# Alimentacion.net
KiCad netlist of a schematic drawn in Altium Designer
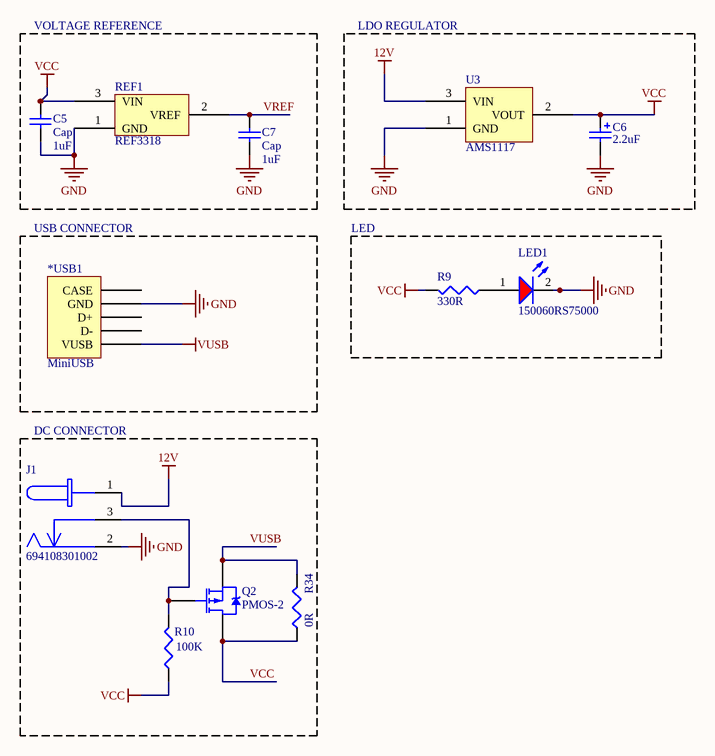
[diagram p0: Alimentacion.SchDoc]

(export (version "E")
  (design (tool "Eeschema 10.0.6"))
  (components
    (comp (ref "*USB1")
      (value "MiniUSB")
      (footprint "Mini USB")
      (description "KYOCERA  24 5141 005 000 863")
      (libsource (lib "Lib_CR") (part "MiniUSB"))
    )
    (comp (ref "C5")
      (value "Cap")
      (footprint "C0805")
      (description "Capacitor")
      (fields (field (name "ALTIUM_VALUE") "1uF") (field (name "PUBLISHER") "Altium Limited"))
      (libsource (lib "Miscellaneous Devices") (part "Cap"))
    )
    (comp (ref "C6")
      (value "2.2uF")
      (footprint "Miscellaneous Devices:C0805")
      (fields (field (name "Comment") "CapPol"))
      (libsource (lib "Library_triggerr") (part "CapPol"))
    )
    (comp (ref "C7")
      (value "Cap")
      (footprint "C0805")
      (description "Capacitor")
      (fields (field (name "ALTIUM_VALUE") "1uF") (field (name "PUBLISHER") "Altium Limited"))
      (libsource (lib "Miscellaneous Devices") (part "Cap"))
    )
    (comp (ref "J1")
      (value "694108301002")
      (footprint "694108301002")
      (description "WR-DC DC Power Jack Right Angled(6.4)")
      (fields (field (name "PUBLISHER") "Wurth Elektronik"))
      (libsource (lib "ALTIUM-WR-DC_POWER_JACK_CONNECTORS-rev1") (part "694108301002"))
    )
    (comp (ref "LED1")
      (value "150060RS75000")
      (footprint "LED_0603_Red")
      (description "SMD mono-color Chip LED, WL-SMCW, Red")
      (fields
        (field (name "MANUFACTURER") "W黵th Elektronik eiSos GmbH")
        (field (name "CREATED BY") "Christin Otto")
      )
      (libsource (lib "WL-SMCW_rev15b") (part "WL-SMCW 0603  150060RS75000"))
    )
    (comp (ref "Q2")
      (value "PMOS-2")
      (footprint "SOT23_N")
      (description "P-Channel Power MOSFET")
      (fields (field (name "PUBLISHER") "Altium Limited"))
      (libsource (lib "Miscellaneous Devices") (part "PMOS-2"))
    )
    (comp (ref "R9")
      (value "330R")
      (footprint "6-0805_N")
      (description "Resistor")
      (fields (field (name "Comment") "Res") (field (name "PUBLISHER") "Altium Limited"))
      (libsource (lib "Miscellaneous Devices") (part "Res3"))
    )
    (comp (ref "R10")
      (value "100K")
      (footprint "6-0805_N")
      (description "Resistor")
      (fields (field (name "Comment") "Res") (field (name "PUBLISHER") "Altium Limited"))
      (libsource (lib "Miscellaneous Devices") (part "Res3"))
    )
    (comp (ref "R34")
      (value "0R")
      (footprint "6-0805_N")
      (description "Resistor")
      (fields (field (name "Comment") "Res") (field (name "PUBLISHER") "Altium Limited"))
      (libsource (lib "Miscellaneous Devices") (part "Res3"))
    )
    (comp (ref "REF1")
      (value "REF3318")
      (footprint "SOT23_N")
      (libsource (lib "Library_triggerr") (part "REF3318"))
    )
    (comp (ref "U3")
      (value "AMS1117")
      (footprint "SOT223_N")
      (libsource (lib "Library_triggerr") (part "AMS1117"))
    )
  )
  (nets
    (net (code "1") (name "/VREF") (class "Default")
      (node (ref "C7") (pin "2") (pinfunction "2_2") (pintype "passive"))
      (node (ref "REF1") (pin "2") (pinfunction "VREF_2") (pintype "passive"))
    )
    (net (code "2") (name "12V") (class "Default")
      (node (ref "J1") (pin "1") (pinfunction "1_1") (pintype "passive"))
      (node (ref "U3") (pin "3") (pinfunction "VIN_3") (pintype "passive"))
    )
    (net (code "3") (name "GND") (class "Default")
      (node (ref "*USB1") (pin "2") (pinfunction "GND_2") (pintype "passive"))
      (node (ref "C5") (pin "1") (pinfunction "1_1") (pintype "passive"))
      (node (ref "C6") (pin "2") (pinfunction "2_2") (pintype "passive"))
      (node (ref "C7") (pin "1") (pinfunction "1_1") (pintype "passive"))
      (node (ref "J1") (pin "2") (pinfunction "2_2") (pintype "passive"))
      (node (ref "LED1") (pin "2") (pinfunction "C_2") (pintype "passive"))
      (node (ref "REF1") (pin "1") (pinfunction "GND_1") (pintype "passive"))
      (node (ref "U3") (pin "1") (pinfunction "GND_1") (pintype "passive"))
    )
    (net (code "4") (name "Net-(LED1-A)") (class "Default")
      (node (ref "LED1") (pin "1") (pinfunction "A_1") (pintype "passive"))
      (node (ref "R9") (pin "1") (pinfunction "1_1") (pintype "passive"))
    )
    (net (code "5") (name "Net-(Q2-G)") (class "Default")
      (node (ref "J1") (pin "3") (pinfunction "3_3") (pintype "passive"))
      (node (ref "Q2") (pin "3") (pinfunction "G_3") (pintype "passive"))
      (node (ref "R10") (pin "2") (pinfunction "2_2") (pintype "passive"))
    )
    (net (code "6") (name "VCC") (class "Default")
      (node (ref "C5") (pin "2") (pinfunction "2_2") (pintype "passive"))
      (node (ref "C6") (pin "1") (pinfunction "1_1") (pintype "passive"))
      (node (ref "Q2") (pin "1") (pinfunction "D_1") (pintype "passive"))
      (node (ref "R10") (pin "1") (pinfunction "1_1") (pintype "passive"))
      (node (ref "R34") (pin "1") (pinfunction "1_1") (pintype "passive"))
      (node (ref "R9") (pin "2") (pinfunction "2_2") (pintype "passive"))
      (node (ref "REF1") (pin "3") (pinfunction "VIN_3") (pintype "passive"))
      (node (ref "U3") (pin "2") (pinfunction "VOUT_2") (pintype "passive"))
    )
    (net (code "7") (name "VUSB") (class "Default")
      (node (ref "*USB1") (pin "6") (pinfunction "VUSB_6") (pintype "passive"))
      (node (ref "Q2") (pin "2") (pinfunction "S_2") (pintype "passive"))
      (node (ref "R34") (pin "2") (pinfunction "2_2") (pintype "passive"))
    )
    (net (code "8") (name "unconnected-(*USB1-CASE-Pad1)") (class "Default")
      (node (ref "*USB1") (pin "1") (pinfunction "CASE_1") (pintype "passive"))
    )
    (net (code "9") (name "unconnected-(*USB1-D+-Pad4)") (class "Default")
      (node (ref "*USB1") (pin "4") (pinfunction "D+_4") (pintype "passive"))
    )
    (net (code "10") (name "unconnected-(*USB1-D--Pad5)") (class "Default")
      (node (ref "*USB1") (pin "5") (pinfunction "D-_5") (pintype "passive"))
    )
  )
)
